# Power_Supply.net
KiCad netlist of a schematic drawn in Altium Designer
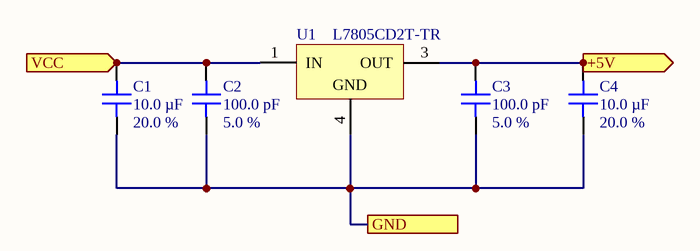
[diagram p0: Power Supply.SchDoc]

(export (version "E")
  (design (tool "Eeschema 10.0.6"))
  (components
    (comp (ref "C1")
      (value "10.0 µF")
      (footprint "PCB - CAPACITOR - MLCC - CAP 0603_1608")
      (description "10 µF ±20% 16V Ceramic Capacitor X5R 0603 (1608 Metric)")
      (fields
        (field (name "ROWAN PART NUMBER") "1572")
        (field (name "TOLERANCE") "20.0 %")
        (field (name "MANUFACTURER") "YAGEO")
      )
      (libsource (lib "RowanAltiumLibrary") (part "SCH - PASSIVES - CAPACITOR"))
    )
    (comp (ref "C2")
      (value "100.0 pF")
      (footprint "PCB - CAPACITOR - MLCC - CAP 0603_1608")
      (description "100 pF ±5% 50V Ceramic Capacitor X7R 0603 (1608 Metric)")
      (fields
        (field (name "ROWAN PART NUMBER") "1535")
        (field (name "TOLERANCE") "5.0 %")
        (field (name "MANUFACTURER") "YAGEO")
      )
      (libsource (lib "RowanAltiumLibrary") (part "SCH - PASSIVES - CAPACITOR"))
    )
    (comp (ref "C3")
      (value "100.0 pF")
      (footprint "PCB - CAPACITOR - MLCC - CAP 0603_1608")
      (description "100 pF ±5% 50V Ceramic Capacitor X7R 0603 (1608 Metric)")
      (fields
        (field (name "ROWAN PART NUMBER") "1535")
        (field (name "TOLERANCE") "5.0 %")
        (field (name "MANUFACTURER") "YAGEO")
      )
      (libsource (lib "RowanAltiumLibrary") (part "SCH - PASSIVES - CAPACITOR"))
    )
    (comp (ref "C4")
      (value "10.0 µF")
      (footprint "PCB - CAPACITOR - MLCC - CAP 0603_1608")
      (description "10 µF ±20% 16V Ceramic Capacitor X5R 0603 (1608 Metric)")
      (fields
        (field (name "ROWAN PART NUMBER") "1572")
        (field (name "TOLERANCE") "20.0 %")
        (field (name "MANUFACTURER") "YAGEO")
      )
      (libsource (lib "RowanAltiumLibrary") (part "SCH - PASSIVES - CAPACITOR"))
    )
    (comp (ref "U1")
      (value "L7805CD2T-TR")
      (footprint "TO-263_M")
      (description "Positive Voltage Regulator, 3-Pin D2PAK, Tape and Reel")
      (libsource (lib "Altium Content Vault") (part "PM-REG-L4940-SOT3"))
    )
  )
  (nets
    (net (code "1") (name "/+5V") (class "Default")
      (node (ref "C3") (pin "2") (pinfunction "2_2") (pintype "passive"))
      (node (ref "C4") (pin "2") (pinfunction "2_2") (pintype "passive"))
      (node (ref "U1") (pin "3") (pinfunction "OUT_3") (pintype "power_in"))
    )
    (net (code "2") (name "/GND") (class "Default")
      (node (ref "C1") (pin "1") (pinfunction "1_1") (pintype "passive"))
      (node (ref "C2") (pin "1") (pinfunction "1_1") (pintype "passive"))
      (node (ref "C3") (pin "1") (pinfunction "1_1") (pintype "passive"))
      (node (ref "C4") (pin "1") (pinfunction "1_1") (pintype "passive"))
      (node (ref "U1") (pin "4") (pinfunction "GND_4") (pintype "power_in"))
    )
    (net (code "3") (name "/VCC") (class "Default")
      (node (ref "C1") (pin "2") (pinfunction "2_2") (pintype "passive"))
      (node (ref "C2") (pin "2") (pinfunction "2_2") (pintype "passive"))
      (node (ref "U1") (pin "1") (pinfunction "IN_1") (pintype "power_in"))
    )
  )
)
